# UI.net
KiCad netlist of a schematic drawn in EAGLE
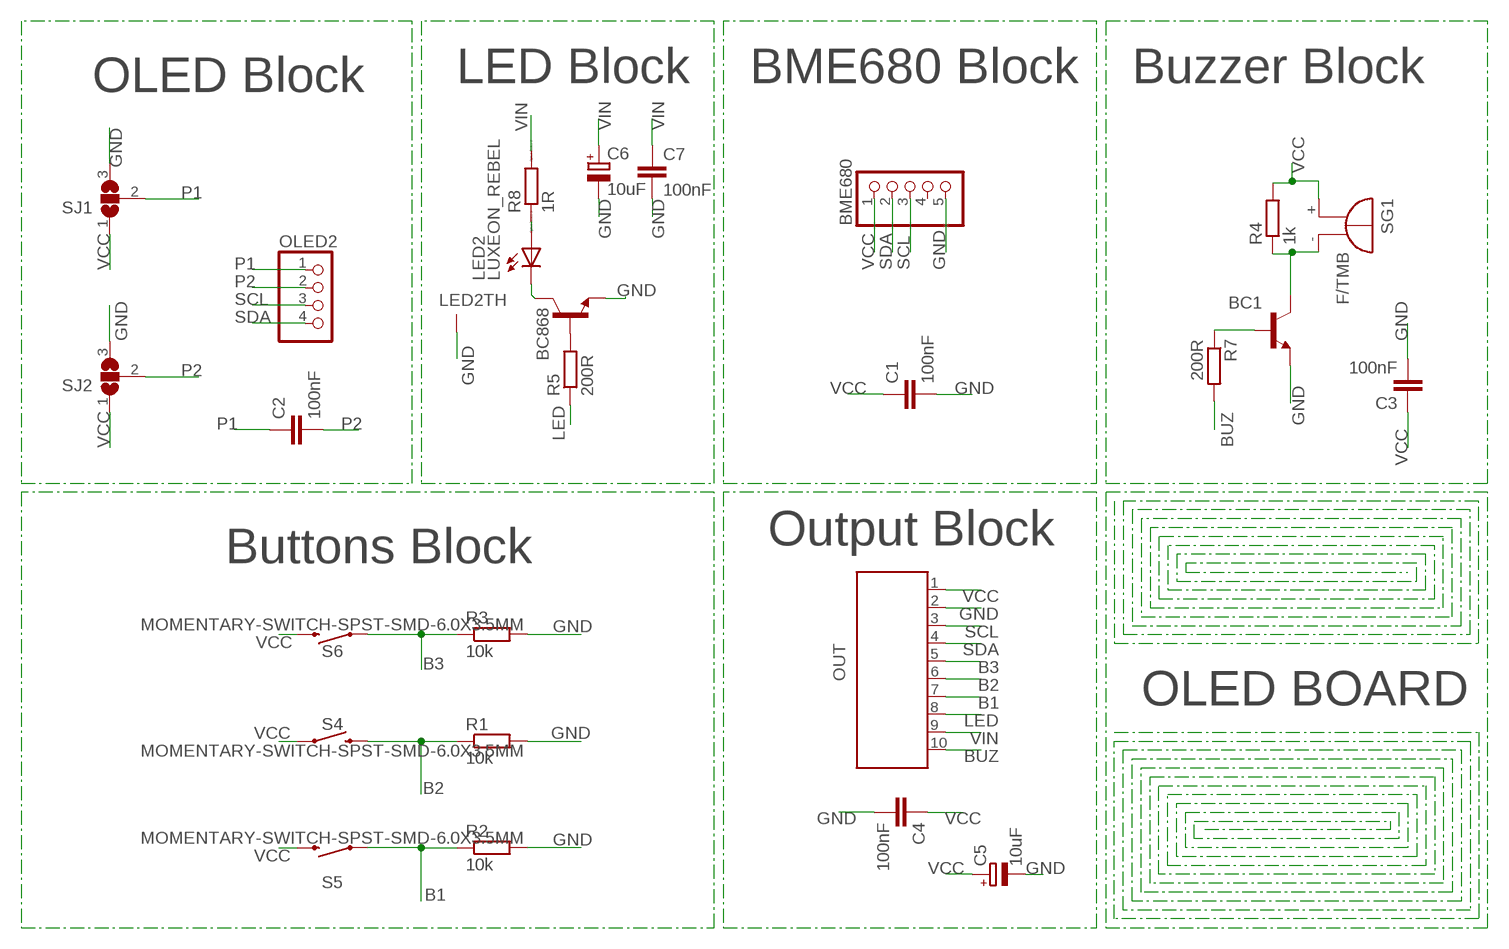
[diagram p0: schematic, sheet 1]

(export (version "E")
  (design (tool "Eeschema 10.0.6"))
  (components
    (comp (ref "BC1")
      (value "BC868-NPN-SOT89-BCE")
      (footprint "eagle-import:SOT89-BCE")
      (libsource (lib "eagle-import") (part "-NPN-SOT89-BCEBC868"))
    )
    (comp (ref "BC868")
      (value "BC868-NPN-SOT89-BCE")
      (footprint "eagle-import:SOT89-BCE")
      (libsource (lib "eagle-import") (part "-NPN-SOT89-BCEBC868"))
    )
    (comp (ref "BME680")
      (value "PINHD-1X5")
      (footprint "eagle-import:1X05")
      (libsource (lib "eagle-import") (part "PINHD-1X5"))
    )
    (comp (ref "C1")
      (value "100nF")
      (footprint "eagle-import:C0805")
      (libsource (lib "eagle-import") (part "C-EUC0805"))
    )
    (comp (ref "C2")
      (value "100nF")
      (footprint "eagle-import:C0805")
      (libsource (lib "eagle-import") (part "C-EUC0805"))
    )
    (comp (ref "C3")
      (value "100nF")
      (footprint "eagle-import:C0805")
      (libsource (lib "eagle-import") (part "C-EUC0805"))
    )
    (comp (ref "C4")
      (value "100nF")
      (footprint "eagle-import:C1808")
      (libsource (lib "eagle-import") (part "C-EUC1808"))
    )
    (comp (ref "C5")
      (value "10uF")
      (footprint "eagle-import:SMC_A")
      (libsource (lib "eagle-import") (part "CPOL-EUSMCA"))
    )
    (comp (ref "C6")
      (value "10uF")
      (footprint "eagle-import:SMC_A")
      (libsource (lib "eagle-import") (part "CPOL-EUSMCA"))
    )
    (comp (ref "C7")
      (value "100nF")
      (footprint "eagle-import:C0805")
      (libsource (lib "eagle-import") (part "C-EUC0805"))
    )
    (comp (ref "LED2")
      (value "LUXEON_REBEL")
      (footprint "eagle-import:LUXEON_REBEL")
      (libsource (lib "eagle-import") (part "LUXEON_REBEL"))
    )
    (comp (ref "OLED2")
      (value "PINHD-1X4")
      (footprint "eagle-import:1X04")
      (libsource (lib "eagle-import") (part "PINHD-1X4"))
    )
    (comp (ref "OUT")
      (value "686110183422")
      (footprint "eagle-import:686110183422")
      (libsource (lib "eagle-import") (part "686110183422"))
    )
    (comp (ref "R1")
      (value "10k")
      (footprint "eagle-import:M1206")
      (fields (field (name "SPICEPREFIX") "10K"))
      (libsource (lib "eagle-import") (part "R-EU_M1206"))
    )
    (comp (ref "R2")
      (value "10k")
      (footprint "eagle-import:M1206")
      (fields (field (name "SPICEPREFIX") "10K"))
      (libsource (lib "eagle-import") (part "R-EU_M1206"))
    )
    (comp (ref "R3")
      (value "10k")
      (footprint "eagle-import:M1206")
      (fields (field (name "SPICEPREFIX") "10K"))
      (libsource (lib "eagle-import") (part "R-EU_M1206"))
    )
    (comp (ref "R4")
      (value "1k")
      (footprint "eagle-import:M0805")
      (fields (field (name "SPICEPREFIX") "10K"))
      (libsource (lib "eagle-import") (part "R-EU_M0805"))
    )
    (comp (ref "R5")
      (value "200R")
      (footprint "eagle-import:M0805")
      (fields (field (name "SPICEPREFIX") "10K"))
      (libsource (lib "eagle-import") (part "R-EU_M0805"))
    )
    (comp (ref "R7")
      (value "200R")
      (footprint "eagle-import:M0805")
      (fields (field (name "SPICEPREFIX") "10K"))
      (libsource (lib "eagle-import") (part "R-EU_M0805"))
    )
    (comp (ref "R8")
      (value "1R")
      (footprint "eagle-import:R3216")
      (libsource (lib "eagle-import") (part "RR3216"))
    )
    (comp (ref "S4")
      (value "MOMENTARY-SWITCH-SPST-SMD-6.0X3.5MM")
      (footprint "eagle-import:TACTILE_SWITCH_SMD_6.0X3.5MM")
      (libsource (lib "eagle-import") (part "MOMENTARY-SWITCH-SPST-SMD-6.0X3.5MM"))
    )
    (comp (ref "S5")
      (value "MOMENTARY-SWITCH-SPST-SMD-6.0X3.5MM")
      (footprint "eagle-import:TACTILE_SWITCH_SMD_6.0X3.5MM")
      (libsource (lib "eagle-import") (part "MOMENTARY-SWITCH-SPST-SMD-6.0X3.5MM"))
    )
    (comp (ref "S6")
      (value "MOMENTARY-SWITCH-SPST-SMD-6.0X3.5MM")
      (footprint "eagle-import:TACTILE_SWITCH_SMD_6.0X3.5MM")
      (libsource (lib "eagle-import") (part "MOMENTARY-SWITCH-SPST-SMD-6.0X3.5MM"))
    )
    (comp (ref "SG1")
      (value "F/TMB")
      (footprint "eagle-import:F_TMB")
      (libsource (lib "eagle-import") (part "F/TMB"))
    )
    (comp (ref "SJ1")
      (value "SJ2W")
      (footprint "eagle-import:SJ_2")
      (libsource (lib "eagle-import") (part "SJ2W"))
    )
    (comp (ref "SJ2")
      (value "SJ2W")
      (footprint "eagle-import:SJ_2")
      (libsource (lib "eagle-import") (part "SJ2W"))
    )
  )
  (nets
    (net (code "1") (name "/B1") (class "Default")
      (node (ref "OUT") (pin "7") (pinfunction "4_7") (pintype "passive"))
      (node (ref "R2") (pin "1") (pinfunction "1_1") (pintype "passive"))
      (node (ref "S5") (pin "1") (pinfunction "1_1") (pintype "passive"))
    )
    (net (code "2") (name "/B2") (class "Default")
      (node (ref "OUT") (pin "6") (pinfunction "5_6") (pintype "passive"))
      (node (ref "R1") (pin "1") (pinfunction "1_1") (pintype "passive"))
      (node (ref "S4") (pin "2") (pinfunction "2_2") (pintype "passive"))
    )
    (net (code "3") (name "/B3") (class "Default")
      (node (ref "OUT") (pin "5") (pinfunction "6_5") (pintype "passive"))
      (node (ref "R3") (pin "1") (pinfunction "1_1") (pintype "passive"))
      (node (ref "S6") (pin "1") (pinfunction "1_1") (pintype "passive"))
    )
    (net (code "4") (name "/BUZ") (class "Default")
      (node (ref "OUT") (pin "10") (pinfunction "1_10") (pintype "passive"))
      (node (ref "R7") (pin "2") (pinfunction "2_2") (pintype "passive"))
    )
    (net (code "5") (name "/GND") (class "Default")
      (node (ref "BC1") (pin "E") (pinfunction "E_E") (pintype "passive"))
      (node (ref "BC868") (pin "E") (pinfunction "E_E") (pintype "passive"))
      (node (ref "BME680") (pin "5") (pinfunction "5_5") (pintype "passive"))
      (node (ref "C1") (pin "2") (pinfunction "2_2") (pintype "passive"))
      (node (ref "C3") (pin "2") (pinfunction "2_2") (pintype "passive"))
      (node (ref "C4") (pin "2") (pinfunction "2_2") (pintype "passive"))
      (node (ref "C5") (pin "-") (pinfunction "-_-") (pintype "passive"))
      (node (ref "C6") (pin "-") (pinfunction "-_-") (pintype "passive"))
      (node (ref "C7") (pin "2") (pinfunction "2_2") (pintype "passive"))
      (node (ref "LED2") (pin "TH") (pinfunction "TH_TH") (pintype "power_in"))
      (node (ref "LED2") (pin "TH@1") (pinfunction "TH_TH@1") (pintype "power_in"))
      (node (ref "LED2") (pin "TH@2") (pinfunction "TH_TH@2") (pintype "power_in"))
      (node (ref "LED2") (pin "TH@3") (pinfunction "TH_TH@3") (pintype "power_in"))
      (node (ref "LED2") (pin "TH@4") (pinfunction "TH_TH@4") (pintype "power_in"))
      (node (ref "OUT") (pin "2") (pinfunction "9_2") (pintype "passive"))
      (node (ref "R1") (pin "2") (pinfunction "2_2") (pintype "passive"))
      (node (ref "R2") (pin "2") (pinfunction "2_2") (pintype "passive"))
      (node (ref "R3") (pin "2") (pinfunction "2_2") (pintype "passive"))
      (node (ref "SJ1") (pin "3") (pinfunction "3_3") (pintype "passive"))
      (node (ref "SJ2") (pin "3") (pinfunction "3_3") (pintype "passive"))
    )
    (net (code "6") (name "/LED") (class "Default")
      (node (ref "OUT") (pin "8") (pinfunction "3_8") (pintype "passive"))
      (node (ref "R5") (pin "1") (pinfunction "1_1") (pintype "passive"))
    )
    (net (code "7") (name "/P1") (class "Default")
      (node (ref "C2") (pin "1") (pinfunction "1_1") (pintype "passive"))
      (node (ref "OLED2") (pin "1") (pinfunction "1_1") (pintype "passive"))
      (node (ref "SJ1") (pin "2") (pinfunction "2_2") (pintype "passive"))
    )
    (net (code "8") (name "/P2") (class "Default")
      (node (ref "C2") (pin "2") (pinfunction "2_2") (pintype "passive"))
      (node (ref "OLED2") (pin "2") (pinfunction "2_2") (pintype "passive"))
      (node (ref "SJ2") (pin "2") (pinfunction "2_2") (pintype "passive"))
    )
    (net (code "9") (name "/SCL") (class "Default")
      (node (ref "BME680") (pin "3") (pinfunction "3_3") (pintype "passive"))
      (node (ref "OLED2") (pin "3") (pinfunction "3_3") (pintype "passive"))
      (node (ref "OUT") (pin "3") (pinfunction "8_3") (pintype "passive"))
    )
    (net (code "10") (name "/SDA") (class "Default")
      (node (ref "BME680") (pin "2") (pinfunction "2_2") (pintype "passive"))
      (node (ref "OLED2") (pin "4") (pinfunction "4_4") (pintype "passive"))
      (node (ref "OUT") (pin "4") (pinfunction "7_4") (pintype "passive"))
    )
    (net (code "11") (name "/VCC") (class "Default")
      (node (ref "BME680") (pin "1") (pinfunction "1_1") (pintype "passive"))
      (node (ref "C1") (pin "1") (pinfunction "1_1") (pintype "passive"))
      (node (ref "C3") (pin "1") (pinfunction "1_1") (pintype "passive"))
      (node (ref "C4") (pin "1") (pinfunction "1_1") (pintype "passive"))
      (node (ref "C5") (pin "+") (pinfunction "+_+") (pintype "passive"))
      (node (ref "OUT") (pin "1") (pinfunction "10_1") (pintype "passive"))
      (node (ref "R4") (pin "2") (pinfunction "2_2") (pintype "passive"))
      (node (ref "S4") (pin "1") (pinfunction "1_1") (pintype "passive"))
      (node (ref "S5") (pin "2") (pinfunction "2_2") (pintype "passive"))
      (node (ref "S6") (pin "2") (pinfunction "2_2") (pintype "passive"))
      (node (ref "SG1") (pin "+") (pinfunction "+_+") (pintype "passive"))
      (node (ref "SJ1") (pin "1") (pinfunction "1_1") (pintype "passive"))
      (node (ref "SJ2") (pin "1") (pinfunction "1_1") (pintype "passive"))
    )
    (net (code "12") (name "/VIN") (class "Default")
      (node (ref "C6") (pin "+") (pinfunction "+_+") (pintype "passive"))
      (node (ref "C7") (pin "1") (pinfunction "1_1") (pintype "passive"))
      (node (ref "OUT") (pin "9") (pinfunction "2_9") (pintype "passive"))
      (node (ref "R8") (pin "2") (pinfunction "2_2") (pintype "passive"))
    )
    (net (code "13") (name "Net-(BC1-PadB)") (class "Default")
      (node (ref "BC1") (pin "B") (pinfunction "B_B") (pintype "passive"))
      (node (ref "R7") (pin "1") (pinfunction "1_1") (pintype "passive"))
    )
    (net (code "14") (name "Net-(BC1-PadC)") (class "Default")
      (node (ref "BC1") (pin "C") (pinfunction "C_C") (pintype "passive"))
      (node (ref "R4") (pin "1") (pinfunction "1_1") (pintype "passive"))
      (node (ref "SG1") (pin "-") (pinfunction "-_-") (pintype "passive"))
    )
    (net (code "15") (name "Net-(BC868-PadB)") (class "Default")
      (node (ref "BC868") (pin "B") (pinfunction "B_B") (pintype "passive"))
      (node (ref "R5") (pin "2") (pinfunction "2_2") (pintype "passive"))
    )
    (net (code "16") (name "Net-(BC868-PadC)") (class "Default")
      (node (ref "BC868") (pin "C") (pinfunction "C_C") (pintype "passive"))
      (node (ref "LED2") (pin "C") (pinfunction "C_C") (pintype "passive"))
      (node (ref "LED2") (pin "C@1") (pinfunction "C_C@1") (pintype "passive"))
    )
    (net (code "17") (name "Net-(LED2-PadA)") (class "Default")
      (node (ref "LED2") (pin "A") (pinfunction "A_A") (pintype "passive"))
      (node (ref "LED2") (pin "A@1") (pinfunction "A_A@1") (pintype "passive"))
      (node (ref "R8") (pin "1") (pinfunction "1_1") (pintype "passive"))
    )
    (net (code "18") (name "unconnected-(BME680-Pad4)") (class "Default")
      (node (ref "BME680") (pin "4") (pinfunction "4_4") (pintype "passive"))
    )
  )
)
